# 12Vin_to_3V3_LDO.net
KiCad netlist of a schematic drawn in Altium Designer
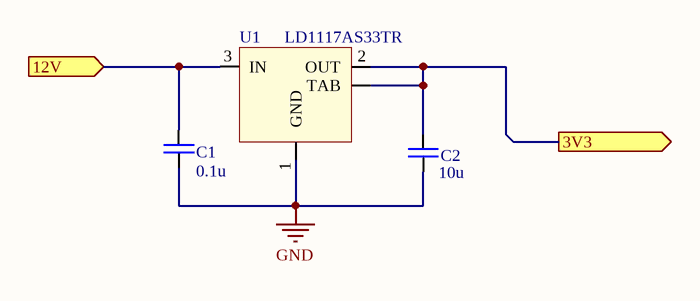
[diagram p0: 12Vin_to_3V3_LDO.SchDoc]

(export (version "E")
  (design (tool "Eeschema 10.0.6"))
  (components
    (comp (ref "C1")
      (value "0.1u")
      (footprint "SMD_components:C0402")
      (description "Chip Capacitor 0402")
      (fields (field (name "VOLTAGE") "25В") (field (name "TOLERANCE") "10%"))
      (libsource (lib "Passives") (part "C0402"))
    )
    (comp (ref "C2")
      (value "10u")
      (footprint "SMD_components:C0805")
      (description "Chip Capacitor 0805")
      (fields (field (name "VOLTAGE") "16В") (field (name "TOLERANCE") "10%"))
      (libsource (lib "Passives") (part "C0805"))
    )
    (comp (ref "U1")
      (value "Микросхема, LD1117AS33TR")
      (footprint "SMD_components:SOT223")
      (description "0.8-A, Positive Fixed-Voltage, Low-Dropout Regulator")
      (fields (field (name "MANUFACTURER") "ST Microelectronics") (field (name "PARTNUMBER") "LD1117AS33TR"))
      (libsource (lib "IC") (part "LD1117AS33TR"))
    )
  )
  (nets
    (net (code "1") (name "/3V3") (class "Default")
      (node (ref "C2") (pin "1") (pinfunction "1_1") (pintype "passive"))
      (node (ref "U1") (pin "2") (pinfunction "OUT_2") (pintype "power_in"))
      (node (ref "U1") (pin "4") (pinfunction "TAB_4") (pintype "passive"))
    )
    (net (code "2") (name "/12V") (class "Default")
      (node (ref "C1") (pin "1") (pinfunction "1_1") (pintype "passive"))
      (node (ref "U1") (pin "3") (pinfunction "IN_3") (pintype "power_in"))
    )
    (net (code "3") (name "GND") (class "Default")
      (node (ref "C1") (pin "2") (pinfunction "2_2") (pintype "passive"))
      (node (ref "C2") (pin "2") (pinfunction "2_2") (pintype "passive"))
      (node (ref "U1") (pin "1") (pinfunction "GND_1") (pintype "power_in"))
    )
  )
)
